# Microphone.net
KiCad netlist of a schematic drawn in Altium Designer
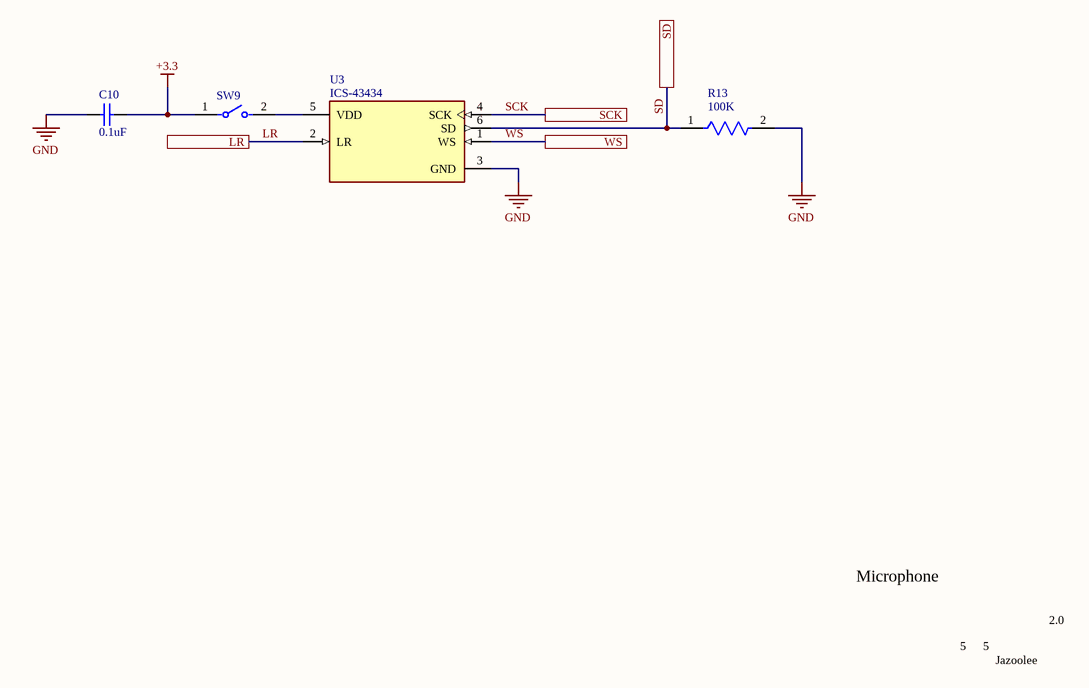
[diagram p0: Microphone.SchDoc]

(export (version "E")
  (design (tool "Eeschema 10.0.6"))
  (components
    (comp (ref "C10")
      (value "0.1uF")
      (footprint "CAPC2013X140X50LL20T25")
      (description "100nF 0805 Ceramic 50V 10%")
      (fields
        (field (name "MANUFACTURER") "AVX Interconnect / Elco")
        (field (name "PART NUMBER") "08055F104KAT2A")
      )
      (libsource (lib "Altium Content Vault") (part "CAP"))
    )
    (comp (ref "R13")
      (value "ERA-6AEB104V")
      (footprint "FP-ERA6A-IPC_B")
      (description "RES 100K OHM 0.1% 1/8W 0805")
      (fields (field (name "TOLERANCE") "0.1%") (field (name "RESISTANCE") "100K"))
      (libsource (lib "Altium Content Vault") (part "1029c3af85768c4190bb7ad29bc67b5"))
    )
    (comp (ref "SW9")
      (value "BD01")
      (footprint "FP-BD01-MFG")
      (description "SWITCH SLIDE DIP SPST 100MA 5V")
      (libsource (lib "Altium Content Vault") (part "bb27bde45df87f1f469753f287ef5ae"))
    )
    (comp (ref "U3")
      (value "ICS-43434")
      (footprint "FP-ICS-43434-MFG")
      (description "ICS-43434 Mic Omni-Directional -26dB 3.63V Rectangular Solder Pad T/R")
      (libsource (lib "Altium Content Vault") (part "ae05e933d23a1a1b08b70095a55dc98"))
    )
  )
  (nets
    (net (code "1") (name "+3.3") (class "Default")
      (node (ref "C10") (pin "1") (pinfunction "1_1") (pintype "passive"))
      (node (ref "SW9") (pin "1") (pinfunction "1_1") (pintype "passive"))
    )
    (net (code "2") (name "/LR") (class "Default")
      (node (ref "U3") (pin "2") (pinfunction "LR_2") (pintype "input"))
    )
    (net (code "3") (name "/SCK") (class "Default")
      (node (ref "U3") (pin "4") (pinfunction "SCK_4") (pintype "input"))
    )
    (net (code "4") (name "/SD") (class "Default")
      (node (ref "R13") (pin "1") (pinfunction "1_1") (pintype "passive"))
      (node (ref "U3") (pin "6") (pinfunction "SD_6") (pintype "output"))
    )
    (net (code "5") (name "/WS") (class "Default")
      (node (ref "U3") (pin "1") (pinfunction "WS_1") (pintype "input"))
    )
    (net (code "6") (name "GND") (class "Default")
      (node (ref "C10") (pin "2") (pinfunction "2_2") (pintype "passive"))
      (node (ref "R13") (pin "2") (pinfunction "2_2") (pintype "passive"))
      (node (ref "U3") (pin "3") (pinfunction "GND_3") (pintype "power_in"))
    )
    (net (code "7") (name "Net-(U3-VDD)") (class "Default")
      (node (ref "SW9") (pin "2") (pinfunction "2_2") (pintype "passive"))
      (node (ref "U3") (pin "5") (pinfunction "VDD_5") (pintype "power_in"))
    )
  )
)
